# msp430_dip_breakout.net
KiCad netlist of a schematic drawn in EAGLE
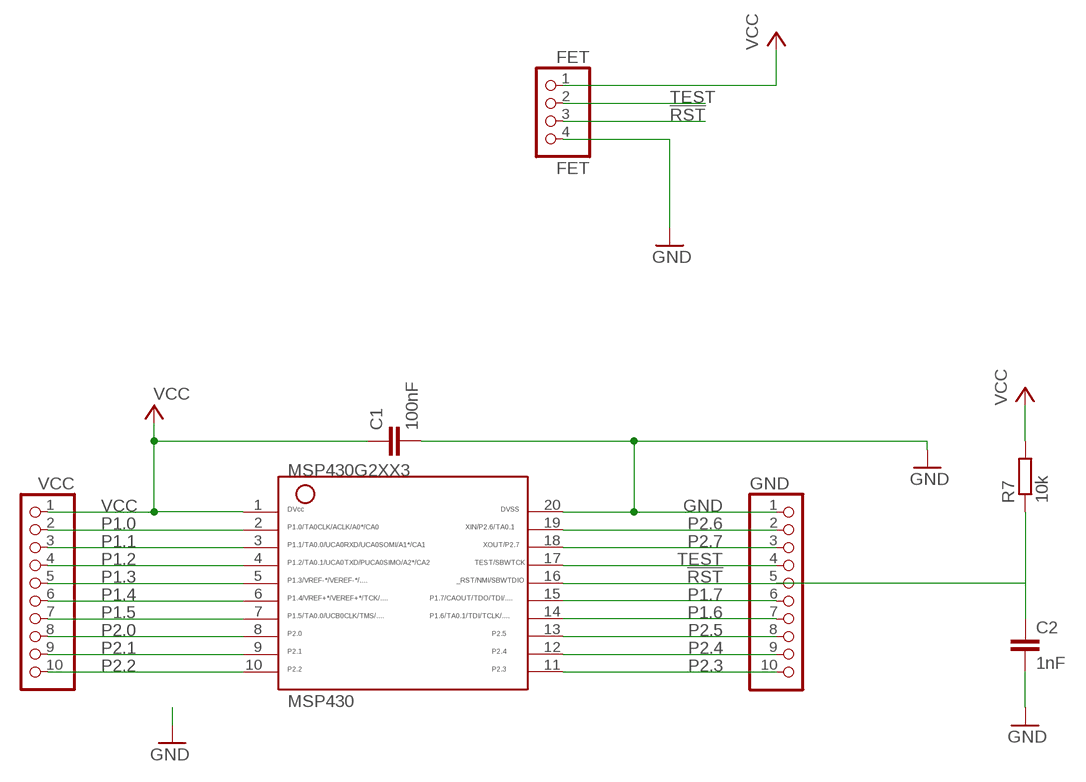
[diagram p0: schematic, sheet 1]

(export (version "E")
  (design (tool "Eeschema 10.0.6"))
  (components
    (comp (ref "C1")
      (value "100nF")
      (footprint "eagle-import:C0805")
      (libsource (lib "eagle-import") (part "C-EUC0805"))
    )
    (comp (ref "C2")
      (value "1nF")
      (footprint "eagle-import:C0805")
      (libsource (lib "eagle-import") (part "C-EUC0805"))
    )
    (comp (ref "FET")
      (value "FET")
      (footprint "eagle-import:1X04")
      (libsource (lib "eagle-import") (part "PINHD-1X4"))
    )
    (comp (ref "GND")
      (value "PH1X10OCT076")
      (footprint "eagle-import:PH1X10OCT76")
      (libsource (lib "eagle-import") (part "PH1X10OCT076"))
    )
    (comp (ref "MSP430")
      (value "MSP430N")
      (footprint "eagle-import:DIP20_HEX")
      (libsource (lib "eagle-import") (part "G2XX3---N20HEX"))
    )
    (comp (ref "R7")
      (value "10k")
      (footprint "eagle-import:R0805")
      (libsource (lib "eagle-import") (part "R-EU_R0805"))
    )
    (comp (ref "VCC")
      (value "PH1X10OCT076")
      (footprint "eagle-import:PH1X10OCT76")
      (libsource (lib "eagle-import") (part "PH1X10OCT076"))
    )
  )
  (nets
    (net (code "1") (name "/P1.0") (class "Default")
      (node (ref "MSP430") (pin "2") (pinfunction "2_2") (pintype "bidirectional"))
      (node (ref "VCC") (pin "2") (pinfunction "2_2") (pintype "passive"))
    )
    (net (code "2") (name "/P1.1") (class "Default")
      (node (ref "MSP430") (pin "3") (pinfunction "3_3") (pintype "bidirectional"))
      (node (ref "VCC") (pin "3") (pinfunction "3_3") (pintype "passive"))
    )
    (net (code "3") (name "/P1.2") (class "Default")
      (node (ref "MSP430") (pin "4") (pinfunction "4_4") (pintype "bidirectional"))
      (node (ref "VCC") (pin "4") (pinfunction "4_4") (pintype "passive"))
    )
    (net (code "4") (name "/P1.3") (class "Default")
      (node (ref "MSP430") (pin "5") (pinfunction "5_5") (pintype "bidirectional"))
      (node (ref "VCC") (pin "5") (pinfunction "5_5") (pintype "passive"))
    )
    (net (code "5") (name "/P1.4") (class "Default")
      (node (ref "MSP430") (pin "6") (pinfunction "6_6") (pintype "bidirectional"))
      (node (ref "VCC") (pin "6") (pinfunction "6_6") (pintype "passive"))
    )
    (net (code "6") (name "/P1.5") (class "Default")
      (node (ref "MSP430") (pin "7") (pinfunction "7_7") (pintype "bidirectional"))
      (node (ref "VCC") (pin "7") (pinfunction "7_7") (pintype "passive"))
    )
    (net (code "7") (name "/P1.6") (class "Default")
      (node (ref "GND") (pin "7") (pinfunction "7_7") (pintype "passive"))
      (node (ref "MSP430") (pin "14") (pinfunction "14_14") (pintype "bidirectional"))
    )
    (net (code "8") (name "/P1.7") (class "Default")
      (node (ref "GND") (pin "6") (pinfunction "6_6") (pintype "passive"))
      (node (ref "MSP430") (pin "15") (pinfunction "15_15") (pintype "bidirectional"))
    )
    (net (code "9") (name "/P2.0") (class "Default")
      (node (ref "MSP430") (pin "8") (pinfunction "8_8") (pintype "bidirectional"))
      (node (ref "VCC") (pin "8") (pinfunction "8_8") (pintype "passive"))
    )
    (net (code "10") (name "/P2.1") (class "Default")
      (node (ref "MSP430") (pin "9") (pinfunction "9_9") (pintype "bidirectional"))
      (node (ref "VCC") (pin "9") (pinfunction "9_9") (pintype "passive"))
    )
    (net (code "11") (name "/P2.2") (class "Default")
      (node (ref "MSP430") (pin "10") (pinfunction "10_10") (pintype "bidirectional"))
      (node (ref "VCC") (pin "10") (pinfunction "10_10") (pintype "passive"))
    )
    (net (code "12") (name "/P2.3") (class "Default")
      (node (ref "GND") (pin "10") (pinfunction "10_10") (pintype "passive"))
      (node (ref "MSP430") (pin "11") (pinfunction "11_11") (pintype "bidirectional"))
    )
    (net (code "13") (name "/P2.4") (class "Default")
      (node (ref "GND") (pin "9") (pinfunction "9_9") (pintype "passive"))
      (node (ref "MSP430") (pin "12") (pinfunction "12_12") (pintype "bidirectional"))
    )
    (net (code "14") (name "/P2.5") (class "Default")
      (node (ref "GND") (pin "8") (pinfunction "8_8") (pintype "passive"))
      (node (ref "MSP430") (pin "13") (pinfunction "13_13") (pintype "bidirectional"))
    )
    (net (code "15") (name "/P2.6") (class "Default")
      (node (ref "GND") (pin "2") (pinfunction "2_2") (pintype "passive"))
      (node (ref "MSP430") (pin "19") (pinfunction "19_19") (pintype "bidirectional"))
    )
    (net (code "16") (name "/P2.7") (class "Default")
      (node (ref "GND") (pin "3") (pinfunction "3_3") (pintype "passive"))
      (node (ref "MSP430") (pin "18") (pinfunction "18_18") (pintype "bidirectional"))
    )
    (net (code "17") (name "/TEST") (class "Default")
      (node (ref "FET") (pin "2") (pinfunction "2_2") (pintype "passive"))
      (node (ref "GND") (pin "4") (pinfunction "4_4") (pintype "passive"))
      (node (ref "MSP430") (pin "17") (pinfunction "17_17") (pintype "bidirectional"))
    )
    (net (code "18") (name "/~{RST}") (class "Default")
      (node (ref "C2") (pin "1") (pinfunction "1_1") (pintype "passive"))
      (node (ref "FET") (pin "3") (pinfunction "3_3") (pintype "passive"))
      (node (ref "GND") (pin "5") (pinfunction "5_5") (pintype "passive"))
      (node (ref "MSP430") (pin "16") (pinfunction "16_16") (pintype "bidirectional"))
      (node (ref "R7") (pin "1") (pinfunction "1_1") (pintype "passive"))
    )
    (net (code "19") (name "GND") (class "Default")
      (node (ref "C1") (pin "2") (pinfunction "2_2") (pintype "passive"))
      (node (ref "C2") (pin "2") (pinfunction "2_2") (pintype "passive"))
      (node (ref "FET") (pin "4") (pinfunction "4_4") (pintype "passive"))
      (node (ref "GND") (pin "1") (pinfunction "1_1") (pintype "passive"))
      (node (ref "MSP430") (pin "20") (pinfunction "20_20") (pintype "bidirectional"))
    )
    (net (code "20") (name "VCC") (class "Default")
      (node (ref "C1") (pin "1") (pinfunction "1_1") (pintype "passive"))
      (node (ref "FET") (pin "1") (pinfunction "1_1") (pintype "passive"))
      (node (ref "MSP430") (pin "1") (pinfunction "1_1") (pintype "bidirectional"))
      (node (ref "R7") (pin "2") (pinfunction "2_2") (pintype "passive"))
      (node (ref "VCC") (pin "1") (pinfunction "1_1") (pintype "passive"))
    )
  )
)
